# EPS.net
KiCad netlist of a schematic drawn in Altium Designer
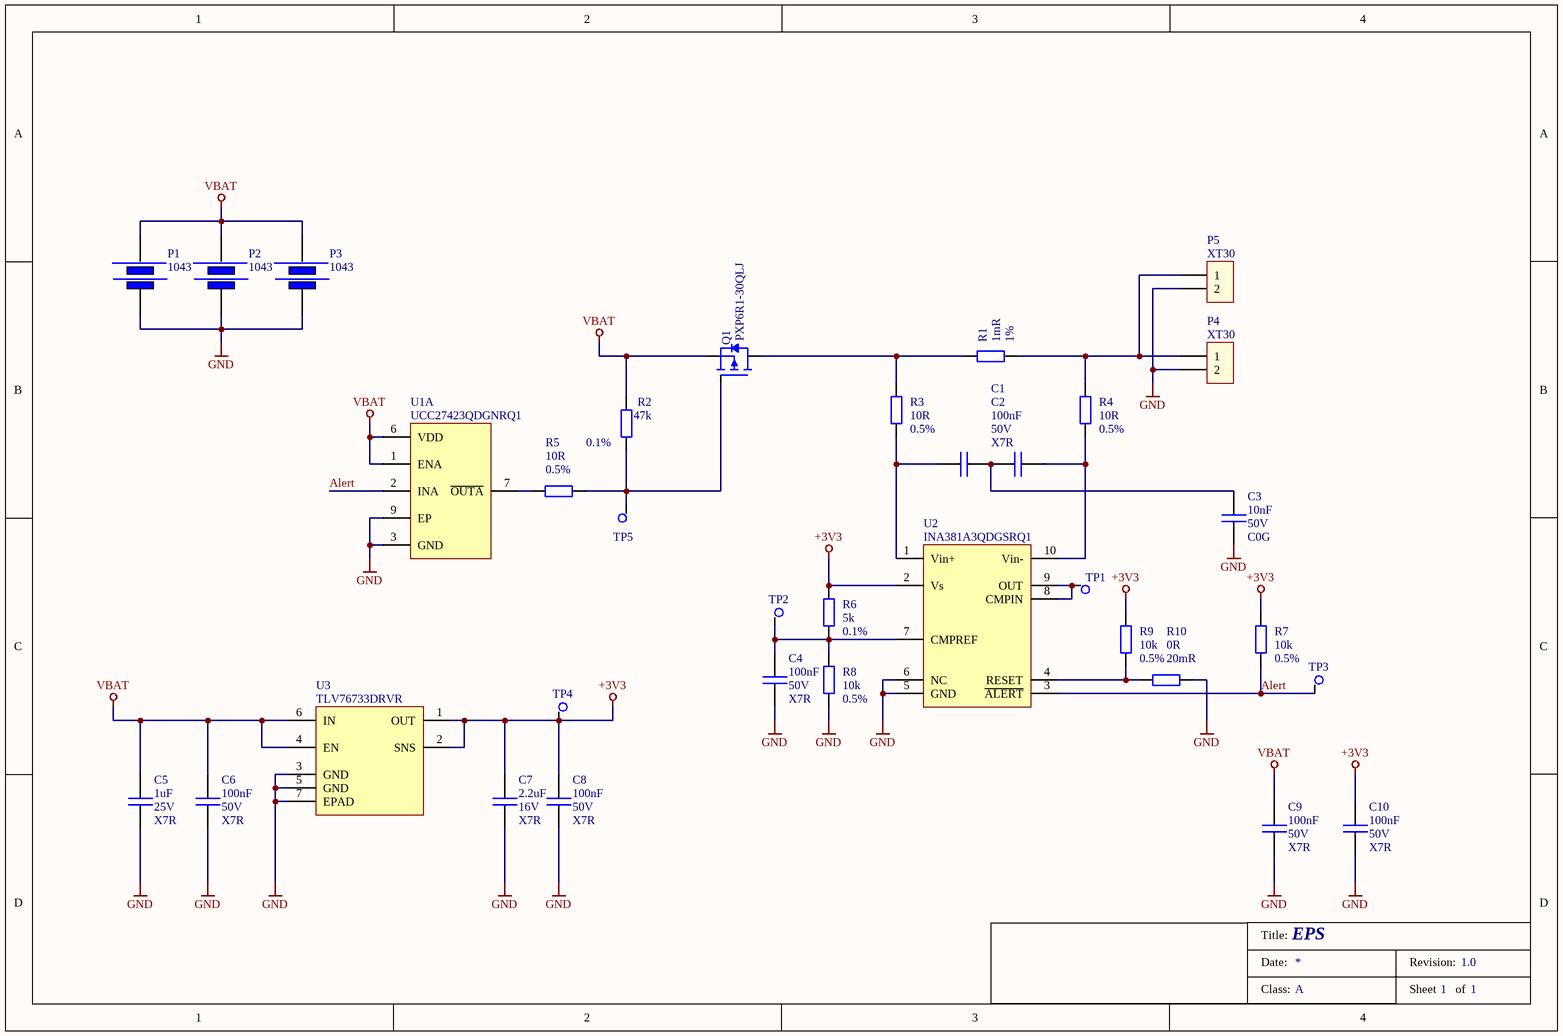
[diagram p0: EPS.SchDoc]

(export (version "E")
  (design (tool "Eeschema 10.0.6"))
  (components
    (comp (ref "C1")
      (value "C")
      (footprint "C_0603")
      (description "Capacitor")
      (fields (field (name "VOLTAGE") "50V") (field (name "PART NUMBER") "C_100nF_50V_0603"))
      (libsource (lib "ProgresjaSpace") (part "C"))
    )
    (comp (ref "C2")
      (value "100nF")
      (footprint "C_0603")
      (description "Capacitor")
      (fields
        (field (name "VOLTAGE") "50V")
        (field (name "DIELECTRIC") "X7R")
        (field (name "PART NUMBER") "C_100nF_50V_0603")
        (field (name "MANUFACTURER") "Kemet")
      )
      (libsource (lib "ProgresjaSpace") (part "C"))
    )
    (comp (ref "C3")
      (value "10nF")
      (footprint "C_0603")
      (description "Capacitor")
      (fields
        (field (name "VOLTAGE") "50V")
        (field (name "DIELECTRIC") "C0G")
        (field (name "PART NUMBER") "C_10nF_50V_0603")
        (field (name "MANUFACTURER") "Kemet")
      )
      (libsource (lib "ProgresjaSpace") (part "C"))
    )
    (comp (ref "C4")
      (value "100nF")
      (footprint "C_0603")
      (description "Capacitor")
      (fields
        (field (name "VOLTAGE") "50V")
        (field (name "DIELECTRIC") "X7R")
        (field (name "PART NUMBER") "C_100nF_50V_0603")
        (field (name "MANUFACTURER") "Kemet")
      )
      (libsource (lib "ProgresjaSpace") (part "C"))
    )
    (comp (ref "C5")
      (value "1uF")
      (footprint "C_0603")
      (description "Capacitor")
      (fields
        (field (name "VOLTAGE") "25V")
        (field (name "DIELECTRIC") "X7R")
        (field (name "PART NUMBER") "C_1uF_25V_0603")
        (field (name "MANUFACTURER") "Murata")
      )
      (libsource (lib "ProgresjaSpace") (part "C"))
    )
    (comp (ref "C6")
      (value "100nF")
      (footprint "C_0603")
      (description "Capacitor")
      (fields
        (field (name "VOLTAGE") "50V")
        (field (name "DIELECTRIC") "X7R")
        (field (name "PART NUMBER") "C_100nF_50V_0603")
        (field (name "MANUFACTURER") "Kemet")
      )
      (libsource (lib "ProgresjaSpace") (part "C"))
    )
    (comp (ref "C7")
      (value "2.2uF")
      (footprint "C_0805")
      (description "Capacitor")
      (fields
        (field (name "VOLTAGE") "16V")
        (field (name "DIELECTRIC") "X7R")
        (field (name "PART NUMBER") "C_2.2uF_16V_0805")
        (field (name "MANUFACTURER") "Kemet")
      )
      (libsource (lib "ProgresjaSpace") (part "C"))
    )
    (comp (ref "C8")
      (value "100nF")
      (footprint "C_0603")
      (description "Capacitor")
      (fields
        (field (name "VOLTAGE") "50V")
        (field (name "DIELECTRIC") "X7R")
        (field (name "PART NUMBER") "C_100nF_50V_0603")
        (field (name "MANUFACTURER") "Kemet")
      )
      (libsource (lib "ProgresjaSpace") (part "C"))
    )
    (comp (ref "C9")
      (value "100nF")
      (footprint "C_0603")
      (description "Capacitor")
      (fields
        (field (name "VOLTAGE") "50V")
        (field (name "DIELECTRIC") "X7R")
        (field (name "PART NUMBER") "C_100nF_50V_0603")
        (field (name "MANUFACTURER") "Kemet")
      )
      (libsource (lib "ProgresjaSpace") (part "C"))
    )
    (comp (ref "C10")
      (value "100nF")
      (footprint "C_0603")
      (description "Capacitor")
      (fields
        (field (name "VOLTAGE") "50V")
        (field (name "DIELECTRIC") "X7R")
        (field (name "PART NUMBER") "C_100nF_50V_0603")
        (field (name "MANUFACTURER") "Kemet")
      )
      (libsource (lib "ProgresjaSpace") (part "C"))
    )
    (comp (ref "P1")
      (value "1043")
      (footprint "B_1043")
      (fields
        (field (name "PART NUMBER") "18650_Holder_1043")
        (field (name "MANUFACTURER") "Keystone Electronics")
        (field (name "Comment") "P_BATT")
      )
      (libsource (lib "ProgresjaSpace") (part "P_BATT"))
    )
    (comp (ref "P2")
      (value "1043")
      (footprint "B_1043")
      (fields
        (field (name "PART NUMBER") "18650_Holder_1043")
        (field (name "MANUFACTURER") "Keystone Electronics")
        (field (name "Comment") "P_BATT")
      )
      (libsource (lib "ProgresjaSpace") (part "P_BATT"))
    )
    (comp (ref "P3")
      (value "1043")
      (footprint "B_1043")
      (fields
        (field (name "PART NUMBER") "18650_Holder_1043")
        (field (name "MANUFACTURER") "Keystone Electronics")
        (field (name "Comment") "P_BATT")
      )
      (libsource (lib "ProgresjaSpace") (part "P_BATT"))
    )
    (comp (ref "P4")
      (value "P_Header_2")
      (footprint "XT30")
      (description "XT30")
      (fields
        (field (name "DESC") "XT30")
        (field (name "MANUFACTURER") "DFRobot")
        (field (name "MANUFACTURER PART NUMBER") "FIT0586")
      )
      (libsource (lib "ProgresjaSpace") (part "P_Header_2"))
    )
    (comp (ref "P5")
      (value "P_Header_2")
      (footprint "XT30")
      (description "XT30")
      (fields
        (field (name "DESC") "XT30")
        (field (name "MANUFACTURER") "DFRobot")
        (field (name "MANUFACTURER PART NUMBER") "FIT0586")
      )
      (libsource (lib "ProgresjaSpace") (part "P_Header_2"))
    )
    (comp (ref "Q1")
      (value "PXP6R1-30QLJ")
      (footprint "WDFN_8")
      (description "Low Vgs Single P-Channel")
      (fields (field (name "MANUFACTURER") "NEXPERIA") (field (name "Comment") "Q_PMOSFET"))
      (libsource (lib "ProgresjaSpace") (part "Q_PMOSFET"))
    )
    (comp (ref "R1")
      (value "1mR")
      (footprint "R_1206")
      (fields
        (field (name "TOLERANCE") "1%")
        (field (name "PART NUMBER") "R_1mR_NA_1206")
        (field (name "VOLTAGE") "NA")
        (field (name "MANUFACTURER") "TT Electronics")
      )
      (libsource (lib "") (part "R_1"))
    )
    (comp (ref "R2")
      (value "47k")
      (footprint "R_0402")
      (fields
        (field (name "TOLERANCE") "0.1%")
        (field (name "PART NUMBER") "R_47k_50V_0402")
        (field (name "VOLTAGE") "50V")
        (field (name "MANUFACTURER") "Vishay")
      )
      (libsource (lib "ProgresjaSpace") (part "R"))
    )
    (comp (ref "R3")
      (value "10R")
      (footprint "R_0603")
      (fields
        (field (name "TOLERANCE") "0.5%")
        (field (name "PART NUMBER") "R_10R_75V_0603")
        (field (name "VOLTAGE") "75V")
        (field (name "MANUFACTURER") "Vishay")
      )
      (libsource (lib "") (part "R_2"))
    )
    (comp (ref "R4")
      (value "10R")
      (footprint "R_0603")
      (fields
        (field (name "TOLERANCE") "0.5%")
        (field (name "PART NUMBER") "R_10R_75V_0603")
        (field (name "VOLTAGE") "75V")
        (field (name "MANUFACTURER") "Vishay")
      )
      (libsource (lib "") (part "R_2"))
    )
    (comp (ref "R5")
      (value "10R")
      (footprint "R_0603")
      (fields
        (field (name "TOLERANCE") "0.5%")
        (field (name "PART NUMBER") "R_10R_75V_0603")
        (field (name "VOLTAGE") "75V")
        (field (name "MANUFACTURER") "Vishay")
      )
      (libsource (lib "") (part "R_1"))
    )
    (comp (ref "R6")
      (value "5k")
      (footprint "R_0603")
      (fields
        (field (name "TOLERANCE") "0.1%")
        (field (name "PART NUMBER") "R_5k_75V_0603")
        (field (name "VOLTAGE") "75V")
        (field (name "MANUFACTURER") "YAGEO")
      )
      (libsource (lib "") (part "R_2"))
    )
    (comp (ref "R7")
      (value "10k")
      (footprint "R_0603")
      (fields
        (field (name "TOLERANCE") "0.5%")
        (field (name "PART NUMBER") "R_10k_75V_0603")
        (field (name "VOLTAGE") "75V")
        (field (name "MANUFACTURER") "Vishay")
      )
      (libsource (lib "") (part "R_2"))
    )
    (comp (ref "R8")
      (value "10k")
      (footprint "R_0603")
      (fields
        (field (name "TOLERANCE") "0.5%")
        (field (name "PART NUMBER") "R_10k_75V_0603")
        (field (name "VOLTAGE") "75V")
        (field (name "MANUFACTURER") "Vishay")
      )
      (libsource (lib "") (part "R_2"))
    )
    (comp (ref "R9")
      (value "10k")
      (footprint "R_0603")
      (fields
        (field (name "TOLERANCE") "0.5%")
        (field (name "PART NUMBER") "R_10k_75V_0603")
        (field (name "VOLTAGE") "75V")
        (field (name "MANUFACTURER") "Vishay")
      )
      (libsource (lib "") (part "R_2"))
    )
    (comp (ref "R10")
      (value "0R")
      (footprint "R_0603")
      (fields
        (field (name "TOLERANCE") "20mR")
        (field (name "PART NUMBER") "R_0R_75V_0603")
        (field (name "VOLTAGE") "75V")
        (field (name "MANUFACTURER") "Vishay")
      )
      (libsource (lib "") (part "R_1"))
    )
    (comp (ref "TP1")
      (value "TP_TestPoint")
      (footprint "TP_01")
      (fields (field (name "PART NUMBER") "TestPoint1") (field (name "MANUFACTURER") "Progresja Space"))
      (libsource (lib "ProgresjaSpace") (part "TP_TestPoint"))
    )
    (comp (ref "TP2")
      (value "TP_TestPoint")
      (footprint "TP_01")
      (fields (field (name "PART NUMBER") "TestPoint1") (field (name "MANUFACTURER") "Progresja Space"))
      (libsource (lib "ProgresjaSpace") (part "TP_TestPoint"))
    )
    (comp (ref "TP3")
      (value "TP_TestPoint")
      (footprint "TP_01")
      (fields (field (name "PART NUMBER") "TestPoint1") (field (name "MANUFACTURER") "Progresja Space"))
      (libsource (lib "ProgresjaSpace") (part "TP_TestPoint"))
    )
    (comp (ref "TP4")
      (value "TP_TestPoint")
      (footprint "TP_01")
      (fields (field (name "PART NUMBER") "TestPoint1") (field (name "MANUFACTURER") "Progresja Space"))
      (libsource (lib "ProgresjaSpace") (part "TP_TestPoint"))
    )
    (comp (ref "TP5")
      (value "TP_TestPoint")
      (footprint "TP_01")
      (fields (field (name "PART NUMBER") "TestPoint1") (field (name "MANUFACTURER") "Progresja Space"))
      (libsource (lib "ProgresjaSpace") (part "TP_TestPoint"))
    )
    (comp (ref "U1")
      (value "UCC27423QDGNRQ1")
      (footprint "MSOP_8")
      (description "Dual 4-A High-Speed Low-Side MOSFET Drivers With Enable")
      (fields (field (name "PART NUMBER") "UCC27423") (field (name "MANUFACTURER") "TI"))
      (libsource (lib "ProgresjaSpace") (part "IC_UCC27423_Q1"))
    )
    (comp (ref "U2")
      (value "INA381A3QDGSRQ1")
      (footprint "VSSOP_10")
      (description "Current Sense Amplifier With Integrated Overcurrent Comparator")
      (fields (field (name "MANUFACTURER") "TI") (field (name "Comment") "IC_INA381_Q1"))
      (libsource (lib "ProgresjaSpace") (part "IC_INA381_Q1"))
    )
    (comp (ref "U3")
      (value "IC_TLV76733DRVR")
      (footprint "WSON_6")
      (description "3.3V LDO Voltage Regulator")
      (fields
        (field (name "=VALUE") "TLV76733DRVR")
        (field (name "PART NUMBER") "TLV76733DRVR")
        (field (name "MANUFACTURER") "TI")
      )
      (libsource (lib "ProgresjaSpace") (part "IC_TLV76733DRVR"))
    )
  )
  (nets
    (net (code "1") (name "+3V3") (class "Default")
      (node (ref "C10") (pin "1") (pinfunction "1_1") (pintype "passive"))
      (node (ref "C7") (pin "1") (pinfunction "1_1") (pintype "passive"))
      (node (ref "C8") (pin "1") (pinfunction "1_1") (pintype "passive"))
      (node (ref "R6") (pin "1") (pinfunction "1_1") (pintype "passive"))
      (node (ref "R7") (pin "1") (pinfunction "1_1") (pintype "passive"))
      (node (ref "R9") (pin "1") (pinfunction "1_1") (pintype "passive"))
      (node (ref "TP4") (pin "1") (pinfunction "1_1") (pintype "passive"))
      (node (ref "U2") (pin "2") (pinfunction "Vs_2") (pintype "passive"))
      (node (ref "U3") (pin "1") (pinfunction "OUT_1") (pintype "passive"))
      (node (ref "U3") (pin "2") (pinfunction "SNS_2") (pintype "passive"))
    )
    (net (code "2") (name "/Alert") (class "Default")
      (node (ref "R7") (pin "2") (pinfunction "2_2") (pintype "passive"))
      (node (ref "TP3") (pin "1") (pinfunction "1_1") (pintype "passive"))
      (node (ref "U1") (pin "2") (pinfunction "INA_2") (pintype "passive"))
      (node (ref "U2") (pin "3") (pinfunction "~{ALERT}_3") (pintype "passive"))
    )
    (net (code "3") (name "GND") (class "Default")
      (node (ref "C10") (pin "2") (pinfunction "2_2") (pintype "passive"))
      (node (ref "C3") (pin "2") (pinfunction "2_2") (pintype "passive"))
      (node (ref "C4") (pin "2") (pinfunction "2_2") (pintype "passive"))
      (node (ref "C5") (pin "2") (pinfunction "2_2") (pintype "passive"))
      (node (ref "C6") (pin "2") (pinfunction "2_2") (pintype "passive"))
      (node (ref "C7") (pin "2") (pinfunction "2_2") (pintype "passive"))
      (node (ref "C8") (pin "2") (pinfunction "2_2") (pintype "passive"))
      (node (ref "C9") (pin "2") (pinfunction "2_2") (pintype "passive"))
      (node (ref "P1") (pin "2") (pintype "passive"))
      (node (ref "P2") (pin "2") (pintype "passive"))
      (node (ref "P3") (pin "2") (pintype "passive"))
      (node (ref "P4") (pin "2") (pinfunction "2_2") (pintype "passive"))
      (node (ref "P5") (pin "2") (pinfunction "2_2") (pintype "passive"))
      (node (ref "R10") (pin "2") (pinfunction "2_2") (pintype "passive"))
      (node (ref "R8") (pin "2") (pinfunction "2_2") (pintype "passive"))
      (node (ref "U1") (pin "3") (pinfunction "GND_3") (pintype "passive"))
      (node (ref "U1") (pin "9") (pinfunction "EP_9") (pintype "passive"))
      (node (ref "U2") (pin "5") (pinfunction "GND_5") (pintype "passive"))
      (node (ref "U2") (pin "6") (pinfunction "NC_6") (pintype "passive"))
      (node (ref "U3") (pin "3") (pinfunction "GND_3") (pintype "passive"))
      (node (ref "U3") (pin "5") (pinfunction "GND_5") (pintype "passive"))
      (node (ref "U3") (pin "7") (pinfunction "EPAD_7") (pintype "passive"))
    )
    (net (code "4") (name "Net-(C1-Pad1)") (class "Default")
      (node (ref "C1") (pin "1") (pinfunction "1_1") (pintype "passive"))
      (node (ref "C2") (pin "2") (pinfunction "2_2") (pintype "passive"))
      (node (ref "C3") (pin "1") (pinfunction "1_1") (pintype "passive"))
    )
    (net (code "5") (name "Net-(P4-Pad1)") (class "Default")
      (node (ref "P4") (pin "1") (pinfunction "1_1") (pintype "passive"))
      (node (ref "P5") (pin "1") (pinfunction "1_1") (pintype "passive"))
      (node (ref "R1") (pin "2") (pinfunction "2_2") (pintype "passive"))
      (node (ref "R4") (pin "1") (pinfunction "1_1") (pintype "passive"))
    )
    (net (code "6") (name "Net-(Q1-D)") (class "Default")
      (node (ref "Q1") (pin "3") (pinfunction "D_3") (pintype "passive"))
      (node (ref "R1") (pin "1") (pinfunction "1_1") (pintype "passive"))
      (node (ref "R3") (pin "1") (pinfunction "1_1") (pintype "passive"))
    )
    (net (code "7") (name "Net-(Q1-G)") (class "Default")
      (node (ref "Q1") (pin "1") (pinfunction "G_1") (pintype "passive"))
      (node (ref "R2") (pin "2") (pinfunction "2_2") (pintype "passive"))
      (node (ref "R5") (pin "2") (pinfunction "2_2") (pintype "passive"))
      (node (ref "TP5") (pin "1") (pinfunction "1_1") (pintype "passive"))
    )
    (net (code "8") (name "Net-(U1A-~{OUTA})") (class "Default")
      (node (ref "R5") (pin "1") (pinfunction "1_1") (pintype "passive"))
      (node (ref "U1") (pin "7") (pinfunction "~{OUTA}_7") (pintype "passive"))
    )
    (net (code "9") (name "Net-(U2-CMPIN)") (class "Default")
      (node (ref "TP1") (pin "1") (pinfunction "1_1") (pintype "passive"))
      (node (ref "U2") (pin "8") (pinfunction "CMPIN_8") (pintype "passive"))
      (node (ref "U2") (pin "9") (pinfunction "OUT_9") (pintype "passive"))
    )
    (net (code "10") (name "Net-(U2-CMPREF)") (class "Default")
      (node (ref "C4") (pin "1") (pinfunction "1_1") (pintype "passive"))
      (node (ref "R6") (pin "2") (pinfunction "2_2") (pintype "passive"))
      (node (ref "R8") (pin "1") (pinfunction "1_1") (pintype "passive"))
      (node (ref "TP2") (pin "1") (pinfunction "1_1") (pintype "passive"))
      (node (ref "U2") (pin "7") (pinfunction "CMPREF_7") (pintype "passive"))
    )
    (net (code "11") (name "Net-(U2-RESET)") (class "Default")
      (node (ref "R10") (pin "1") (pinfunction "1_1") (pintype "passive"))
      (node (ref "R9") (pin "2") (pinfunction "2_2") (pintype "passive"))
      (node (ref "U2") (pin "4") (pinfunction "RESET_4") (pintype "passive"))
    )
    (net (code "12") (name "Net-(U2-Vin+)") (class "Default")
      (node (ref "C2") (pin "1") (pinfunction "1_1") (pintype "passive"))
      (node (ref "R3") (pin "2") (pinfunction "2_2") (pintype "passive"))
      (node (ref "U2") (pin "1") (pinfunction "Vin+_1") (pintype "passive"))
    )
    (net (code "13") (name "Net-(U2-Vin-)") (class "Default")
      (node (ref "C1") (pin "2") (pinfunction "2_2") (pintype "passive"))
      (node (ref "R4") (pin "2") (pinfunction "2_2") (pintype "passive"))
      (node (ref "U2") (pin "10") (pinfunction "Vin-_10") (pintype "passive"))
    )
    (net (code "14") (name "VBAT") (class "Default")
      (node (ref "C5") (pin "1") (pinfunction "1_1") (pintype "passive"))
      (node (ref "C6") (pin "1") (pinfunction "1_1") (pintype "passive"))
      (node (ref "C9") (pin "1") (pinfunction "1_1") (pintype "passive"))
      (node (ref "P1") (pin "1") (pintype "passive"))
      (node (ref "P2") (pin "1") (pintype "passive"))
      (node (ref "P3") (pin "1") (pintype "passive"))
      (node (ref "Q1") (pin "2") (pinfunction "S_2") (pintype "passive"))
      (node (ref "R2") (pin "1") (pinfunction "1_1") (pintype "passive"))
      (node (ref "U1") (pin "1") (pinfunction "ENA_1") (pintype "passive"))
      (node (ref "U1") (pin "6") (pinfunction "VDD_6") (pintype "passive"))
      (node (ref "U3") (pin "4") (pinfunction "EN_4") (pintype "passive"))
      (node (ref "U3") (pin "6") (pinfunction "IN_6") (pintype "passive"))
    )
  )
)
